# shock_side_control.net
KiCad netlist of a schematic drawn in EAGLE
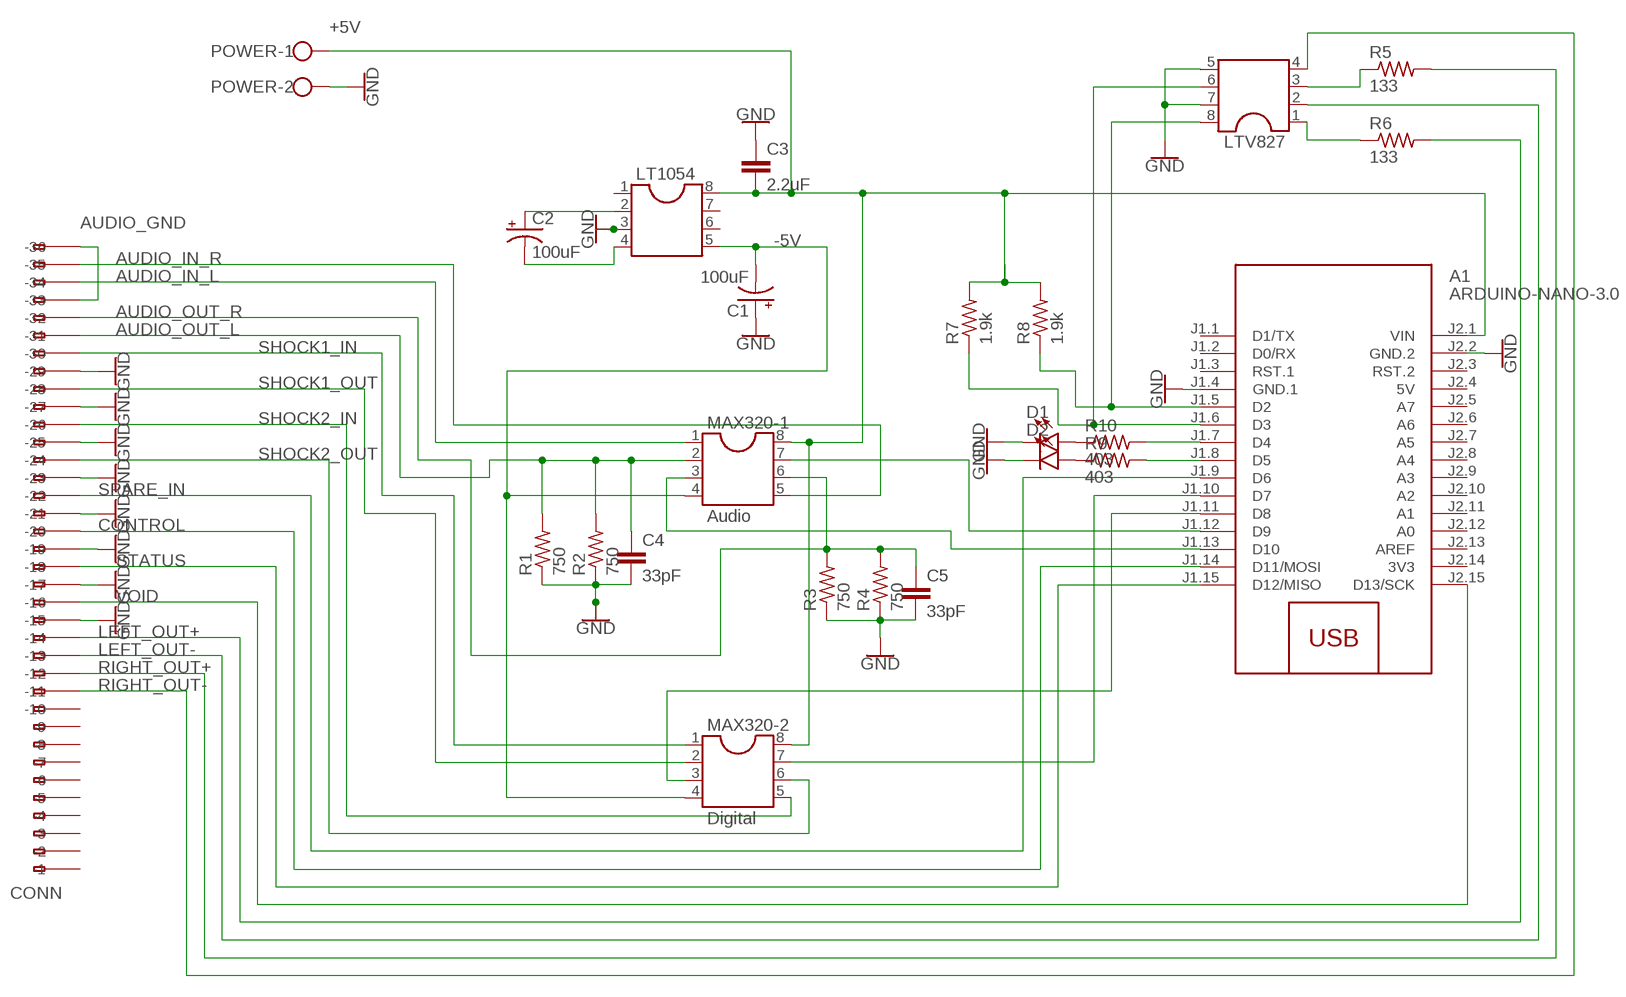
[diagram p0: schematic, sheet 1]

(export (version "E")
  (design (tool "Eeschema 10.0.6"))
  (components
    (comp (ref "A1")
      (value "ARDUINO-NANO-3.0")
      (footprint "eagle-import:ARDUINO-NANO-3.0")
      (libsource (lib "eagle-import") (part "ARDUINO-NANO-3.0"))
    )
    (comp (ref "C1")
      (value "100uF")
      (footprint "eagle-import:CPOL-RADIAL-2.5MM-6.5MM")
      (libsource (lib "eagle-import") (part "100UF-POLAR-RADIAL-2.5MM-25V-20%"))
    )
    (comp (ref "C2")
      (value "100uF")
      (footprint "eagle-import:CPOL-RADIAL-2.5MM-6.5MM")
      (libsource (lib "eagle-import") (part "100UF-POLAR-RADIAL-2.5MM-25V-20%"))
    )
    (comp (ref "C3")
      (value "2.2uF")
      (footprint "eagle-import:C5B2.5")
      (libsource (lib "eagle-import") (part "C5/2.5"))
    )
    (comp (ref "C4")
      (value "33pF")
      (footprint "eagle-import:C5B2.5")
      (libsource (lib "eagle-import") (part "C5/2.5"))
    )
    (comp (ref "C5")
      (value "33pF")
      (footprint "eagle-import:C5B2.5")
      (libsource (lib "eagle-import") (part "C5/2.5"))
    )
    (comp (ref "CONN")
      (value "233-136")
      (footprint "eagle-import:233-136")
      (libsource (lib "eagle-import") (part "233-136"))
    )
    (comp (ref "D1")
      (value "LED-3MM-NO_SILK")
      (footprint "eagle-import:LED_3MM-NS")
      (libsource (lib "eagle-import") (part "LED-3MM-NO_SILK"))
    )
    (comp (ref "D2")
      (value "LED-3MM-NO_SILK")
      (footprint "eagle-import:LED_3MM-NS")
      (libsource (lib "eagle-import") (part "LED-3MM-NO_SILK"))
    )
    (comp (ref "LT1054")
      (value "DIL8")
      (footprint "eagle-import:DIL08")
      (libsource (lib "eagle-import") (part "DIL8"))
    )
    (comp (ref "LTV827")
      (value "DIL8")
      (footprint "eagle-import:DIL08")
      (libsource (lib "eagle-import") (part "DIL8"))
    )
    (comp (ref "MAX320-1")
      (value "Audio")
      (footprint "eagle-import:DIL08")
      (libsource (lib "eagle-import") (part "DIL8"))
    )
    (comp (ref "MAX320-2")
      (value "Digital")
      (footprint "eagle-import:DIL08")
      (libsource (lib "eagle-import") (part "DIL8"))
    )
    (comp (ref "POWER")
      (value "W237-02P")
      (footprint "eagle-import:W237-132")
      (libsource (lib "eagle-import") (part "W237-02P"))
    )
    (comp (ref "R1")
      (value "750")
      (footprint "eagle-import:0805-THM")
      (libsource (lib "eagle-import") (part "FLIPFLOP-RES"))
    )
    (comp (ref "R2")
      (value "750")
      (footprint "eagle-import:0805-THM")
      (libsource (lib "eagle-import") (part "FLIPFLOP-RES"))
    )
    (comp (ref "R3")
      (value "750")
      (footprint "eagle-import:0805-THM")
      (libsource (lib "eagle-import") (part "FLIPFLOP-RES"))
    )
    (comp (ref "R4")
      (value "750")
      (footprint "eagle-import:0805-THM")
      (libsource (lib "eagle-import") (part "FLIPFLOP-RES"))
    )
    (comp (ref "R5")
      (value "133")
      (footprint "eagle-import:0805-THM")
      (libsource (lib "eagle-import") (part "FLIPFLOP-RES"))
    )
    (comp (ref "R6")
      (value "133")
      (footprint "eagle-import:0805-THM")
      (libsource (lib "eagle-import") (part "FLIPFLOP-RES"))
    )
    (comp (ref "R7")
      (value "1.9k")
      (footprint "eagle-import:0805-THM")
      (libsource (lib "eagle-import") (part "FLIPFLOP-RES"))
    )
    (comp (ref "R8")
      (value "1.9k")
      (footprint "eagle-import:0805-THM")
      (libsource (lib "eagle-import") (part "FLIPFLOP-RES"))
    )
    (comp (ref "R9")
      (value "403")
      (footprint "eagle-import:0805-THM")
      (libsource (lib "eagle-import") (part "FLIPFLOP-RES"))
    )
    (comp (ref "R10")
      (value "403")
      (footprint "eagle-import:0805-THM")
      (libsource (lib "eagle-import") (part "FLIPFLOP-RES"))
    )
  )
  (nets
    (net (code "1") (name "/+5V") (class "Default")
      (node (ref "A1") (pin "J2.1") (pinfunction "VIN_J2.1") (pintype "power_in"))
      (node (ref "C3") (pin "2") (pinfunction "2_2") (pintype "passive"))
      (node (ref "LT1054") (pin "8") (pinfunction "8_8") (pintype "passive"))
      (node (ref "MAX320-1") (pin "8") (pinfunction "8_8") (pintype "passive"))
      (node (ref "MAX320-2") (pin "8") (pinfunction "8_8") (pintype "passive"))
      (node (ref "POWER") (pin "1") (pinfunction "KL_1") (pintype "passive"))
      (node (ref "R7") (pin "2") (pinfunction "2_2") (pintype "passive"))
      (node (ref "R8") (pin "2") (pinfunction "2_2") (pintype "passive"))
    )
    (net (code "2") (name "/-5V") (class "Default")
      (node (ref "C1") (pin "2") (pinfunction "-_2") (pintype "passive"))
      (node (ref "LT1054") (pin "5") (pinfunction "5_5") (pintype "passive"))
      (node (ref "MAX320-1") (pin "4") (pinfunction "4_4") (pintype "passive"))
      (node (ref "MAX320-2") (pin "4") (pinfunction "4_4") (pintype "passive"))
    )
    (net (code "3") (name "/3V3") (class "Default")
      (node (ref "A1") (pin "J2.14") (pinfunction "3V3_J2.14") (pintype "power_in"))
    )
    (net (code "4") (name "/5V") (class "Default")
      (node (ref "A1") (pin "J2.4") (pinfunction "5V_J2.4") (pintype "power_in"))
    )
    (net (code "5") (name "/AUDIO_GND") (class "Default")
      (node (ref "CONN") (pin "A33") (pinfunction "-33_A33") (pintype "passive"))
      (node (ref "CONN") (pin "A36") (pinfunction "-36_A36") (pintype "passive"))
    )
    (net (code "6") (name "/AUDIO_IN_L") (class "Default")
      (node (ref "CONN") (pin "A34") (pinfunction "-34_A34") (pintype "passive"))
      (node (ref "MAX320-1") (pin "1") (pinfunction "1_1") (pintype "passive"))
    )
    (net (code "7") (name "/AUDIO_IN_R") (class "Default")
      (node (ref "CONN") (pin "A35") (pinfunction "-35_A35") (pintype "passive"))
      (node (ref "MAX320-1") (pin "5") (pinfunction "5_5") (pintype "passive"))
    )
    (net (code "8") (name "/AUDIO_OUT_L") (class "Default")
      (node (ref "C4") (pin "1") (pinfunction "1_1") (pintype "passive"))
      (node (ref "CONN") (pin "A31") (pinfunction "-31_A31") (pintype "passive"))
      (node (ref "MAX320-1") (pin "2") (pinfunction "2_2") (pintype "passive"))
      (node (ref "R1") (pin "2") (pinfunction "2_2") (pintype "passive"))
      (node (ref "R2") (pin "2") (pinfunction "2_2") (pintype "passive"))
    )
    (net (code "9") (name "/AUDIO_OUT_R") (class "Default")
      (node (ref "C5") (pin "1") (pinfunction "1_1") (pintype "passive"))
      (node (ref "CONN") (pin "A32") (pinfunction "-32_A32") (pintype "passive"))
      (node (ref "MAX320-1") (pin "6") (pinfunction "6_6") (pintype "passive"))
      (node (ref "R3") (pin "2") (pinfunction "2_2") (pintype "passive"))
      (node (ref "R4") (pin "2") (pinfunction "2_2") (pintype "passive"))
    )
    (net (code "10") (name "/CONTROL") (class "Default")
      (node (ref "A1") (pin "J1.14") (pinfunction "D11/MOSI_J1.14") (pintype "bidirectional"))
      (node (ref "CONN") (pin "A20") (pinfunction "-20_A20") (pintype "passive"))
    )
    (net (code "11") (name "/LEFT_OUT+") (class "Default")
      (node (ref "CONN") (pin "A14") (pinfunction "-14_A14") (pintype "passive"))
      (node (ref "R6") (pin "2") (pinfunction "2_2") (pintype "passive"))
    )
    (net (code "12") (name "/LEFT_OUT-") (class "Default")
      (node (ref "CONN") (pin "A13") (pinfunction "-13_A13") (pintype "passive"))
      (node (ref "LTV827") (pin "2") (pinfunction "2_2") (pintype "passive"))
    )
    (net (code "13") (name "/RIGHT_OUT+") (class "Default")
      (node (ref "CONN") (pin "A12") (pinfunction "-12_A12") (pintype "passive"))
      (node (ref "R5") (pin "2") (pinfunction "2_2") (pintype "passive"))
    )
    (net (code "14") (name "/RIGHT_OUT-") (class "Default")
      (node (ref "CONN") (pin "A11") (pinfunction "-11_A11") (pintype "passive"))
      (node (ref "LTV827") (pin "4") (pinfunction "4_4") (pintype "passive"))
    )
    (net (code "15") (name "/SHOCK1_IN") (class "Default")
      (node (ref "CONN") (pin "A30") (pinfunction "-30_A30") (pintype "passive"))
      (node (ref "MAX320-2") (pin "1") (pinfunction "1_1") (pintype "passive"))
    )
    (net (code "16") (name "/SHOCK1_OUT") (class "Default")
      (node (ref "CONN") (pin "A28") (pinfunction "-28_A28") (pintype "passive"))
      (node (ref "MAX320-2") (pin "2") (pinfunction "2_2") (pintype "passive"))
    )
    (net (code "17") (name "/SHOCK2_IN") (class "Default")
      (node (ref "CONN") (pin "A26") (pinfunction "-26_A26") (pintype "passive"))
      (node (ref "MAX320-2") (pin "5") (pinfunction "5_5") (pintype "passive"))
    )
    (net (code "18") (name "/SHOCK2_OUT") (class "Default")
      (node (ref "CONN") (pin "A24") (pinfunction "-24_A24") (pintype "passive"))
      (node (ref "MAX320-2") (pin "6") (pinfunction "6_6") (pintype "passive"))
    )
    (net (code "19") (name "/SPARE_IN") (class "Default")
      (node (ref "A1") (pin "J1.9") (pinfunction "D6_J1.9") (pintype "bidirectional"))
      (node (ref "CONN") (pin "A22") (pinfunction "-22_A22") (pintype "passive"))
    )
    (net (code "20") (name "/STATUS") (class "Default")
      (node (ref "A1") (pin "J1.15") (pinfunction "D12/MISO_J1.15") (pintype "bidirectional"))
      (node (ref "CONN") (pin "A18") (pinfunction "-18_A18") (pintype "passive"))
    )
    (net (code "21") (name "/VOID") (class "Default")
      (node (ref "A1") (pin "J2.15") (pinfunction "D13/SCK_J2.15") (pintype "bidirectional"))
      (node (ref "CONN") (pin "A16") (pinfunction "-16_A16") (pintype "passive"))
    )
    (net (code "22") (name "GND") (class "Default")
      (node (ref "A1") (pin "J1.4") (pinfunction "GND.1_J1.4") (pintype "power_in"))
      (node (ref "A1") (pin "J2.2") (pinfunction "GND.2_J2.2") (pintype "power_in"))
      (node (ref "C1") (pin "1") (pinfunction "+_1") (pintype "passive"))
      (node (ref "C3") (pin "1") (pinfunction "1_1") (pintype "passive"))
      (node (ref "C4") (pin "2") (pinfunction "2_2") (pintype "passive"))
      (node (ref "C5") (pin "2") (pinfunction "2_2") (pintype "passive"))
      (node (ref "CONN") (pin "A15") (pinfunction "-15_A15") (pintype "passive"))
      (node (ref "CONN") (pin "A17") (pinfunction "-17_A17") (pintype "passive"))
      (node (ref "CONN") (pin "A19") (pinfunction "-19_A19") (pintype "passive"))
      (node (ref "CONN") (pin "A21") (pinfunction "-21_A21") (pintype "passive"))
      (node (ref "CONN") (pin "A23") (pinfunction "-23_A23") (pintype "passive"))
      (node (ref "CONN") (pin "A25") (pinfunction "-25_A25") (pintype "passive"))
      (node (ref "CONN") (pin "A27") (pinfunction "-27_A27") (pintype "passive"))
      (node (ref "CONN") (pin "A29") (pinfunction "-29_A29") (pintype "passive"))
      (node (ref "D1") (pin "K") (pinfunction "C_K") (pintype "passive"))
      (node (ref "D2") (pin "K") (pinfunction "C_K") (pintype "passive"))
      (node (ref "LT1054") (pin "3") (pinfunction "3_3") (pintype "passive"))
      (node (ref "LTV827") (pin "5") (pinfunction "5_5") (pintype "passive"))
      (node (ref "LTV827") (pin "7") (pinfunction "7_7") (pintype "passive"))
      (node (ref "POWER") (pin "2") (pinfunction "KL_2") (pintype "passive"))
      (node (ref "R1") (pin "1") (pinfunction "1_1") (pintype "passive"))
      (node (ref "R2") (pin "1") (pinfunction "1_1") (pintype "passive"))
      (node (ref "R3") (pin "1") (pinfunction "1_1") (pintype "passive"))
      (node (ref "R4") (pin "1") (pinfunction "1_1") (pintype "passive"))
    )
    (net (code "23") (name "Net-(A1-D2)") (class "Default")
      (node (ref "A1") (pin "J1.5") (pinfunction "D2_J1.5") (pintype "bidirectional"))
      (node (ref "LTV827") (pin "8") (pinfunction "8_8") (pintype "passive"))
      (node (ref "R8") (pin "1") (pinfunction "1_1") (pintype "passive"))
    )
    (net (code "24") (name "Net-(A1-D3)") (class "Default")
      (node (ref "A1") (pin "J1.6") (pinfunction "D3_J1.6") (pintype "bidirectional"))
      (node (ref "LTV827") (pin "6") (pinfunction "6_6") (pintype "passive"))
      (node (ref "R7") (pin "1") (pinfunction "1_1") (pintype "passive"))
    )
    (net (code "25") (name "Net-(A1-D4)") (class "Default")
      (node (ref "A1") (pin "J1.7") (pinfunction "D4_J1.7") (pintype "bidirectional"))
      (node (ref "R10") (pin "2") (pinfunction "2_2") (pintype "passive"))
    )
    (net (code "26") (name "Net-(A1-D5)") (class "Default")
      (node (ref "A1") (pin "J1.8") (pinfunction "D5_J1.8") (pintype "bidirectional"))
      (node (ref "R9") (pin "2") (pinfunction "2_2") (pintype "passive"))
    )
    (net (code "27") (name "Net-(A1-D7)") (class "Default")
      (node (ref "A1") (pin "J1.10") (pinfunction "D7_J1.10") (pintype "bidirectional"))
      (node (ref "MAX320-2") (pin "7") (pinfunction "7_7") (pintype "passive"))
    )
    (net (code "28") (name "Net-(A1-D8)") (class "Default")
      (node (ref "A1") (pin "J1.11") (pinfunction "D8_J1.11") (pintype "bidirectional"))
      (node (ref "MAX320-2") (pin "3") (pinfunction "3_3") (pintype "passive"))
    )
    (net (code "29") (name "Net-(A1-D9)") (class "Default")
      (node (ref "A1") (pin "J1.12") (pinfunction "D9_J1.12") (pintype "bidirectional"))
      (node (ref "MAX320-1") (pin "7") (pinfunction "7_7") (pintype "passive"))
    )
    (net (code "30") (name "Net-(A1-D10)") (class "Default")
      (node (ref "A1") (pin "J1.13") (pinfunction "D10_J1.13") (pintype "bidirectional"))
      (node (ref "MAX320-1") (pin "3") (pinfunction "3_3") (pintype "passive"))
    )
    (net (code "31") (name "Net-(C2-+)") (class "Default")
      (node (ref "C2") (pin "1") (pinfunction "+_1") (pintype "passive"))
      (node (ref "LT1054") (pin "2") (pinfunction "2_2") (pintype "passive"))
    )
    (net (code "32") (name "Net-(C2--)") (class "Default")
      (node (ref "C2") (pin "2") (pinfunction "-_2") (pintype "passive"))
      (node (ref "LT1054") (pin "4") (pinfunction "4_4") (pintype "passive"))
    )
    (net (code "33") (name "Net-(D1-PadA)") (class "Default")
      (node (ref "D1") (pin "A") (pinfunction "A_A") (pintype "passive"))
      (node (ref "R10") (pin "1") (pinfunction "1_1") (pintype "passive"))
    )
    (net (code "34") (name "Net-(D2-PadA)") (class "Default")
      (node (ref "D2") (pin "A") (pinfunction "A_A") (pintype "passive"))
      (node (ref "R9") (pin "1") (pinfunction "1_1") (pintype "passive"))
    )
    (net (code "35") (name "Net-(LTV827-Pad1)") (class "Default")
      (node (ref "LTV827") (pin "1") (pinfunction "1_1") (pintype "passive"))
      (node (ref "R6") (pin "1") (pinfunction "1_1") (pintype "passive"))
    )
    (net (code "36") (name "Net-(LTV827-Pad3)") (class "Default")
      (node (ref "LTV827") (pin "3") (pinfunction "3_3") (pintype "passive"))
      (node (ref "R5") (pin "1") (pinfunction "1_1") (pintype "passive"))
    )
    (net (code "37") (name "unconnected-(A1-A0-PadJ2.12)") (class "Default")
      (node (ref "A1") (pin "J2.12") (pinfunction "A0_J2.12") (pintype "bidirectional"))
    )
    (net (code "38") (name "unconnected-(A1-A1-PadJ2.11)") (class "Default")
      (node (ref "A1") (pin "J2.11") (pinfunction "A1_J2.11") (pintype "bidirectional"))
    )
    (net (code "39") (name "unconnected-(A1-A2-PadJ2.10)") (class "Default")
      (node (ref "A1") (pin "J2.10") (pinfunction "A2_J2.10") (pintype "bidirectional"))
    )
    (net (code "40") (name "unconnected-(A1-A3-PadJ2.9)") (class "Default")
      (node (ref "A1") (pin "J2.9") (pinfunction "A3_J2.9") (pintype "bidirectional"))
    )
    (net (code "41") (name "unconnected-(A1-A4-PadJ2.8)") (class "Default")
      (node (ref "A1") (pin "J2.8") (pinfunction "A4_J2.8") (pintype "bidirectional"))
    )
    (net (code "42") (name "unconnected-(A1-A5-PadJ2.7)") (class "Default")
      (node (ref "A1") (pin "J2.7") (pinfunction "A5_J2.7") (pintype "bidirectional"))
    )
    (net (code "43") (name "unconnected-(A1-A6-PadJ2.6)") (class "Default")
      (node (ref "A1") (pin "J2.6") (pinfunction "A6_J2.6") (pintype "bidirectional"))
    )
    (net (code "44") (name "unconnected-(A1-A7-PadJ2.5)") (class "Default")
      (node (ref "A1") (pin "J2.5") (pinfunction "A7_J2.5") (pintype "bidirectional"))
    )
    (net (code "45") (name "unconnected-(A1-AREF-PadJ2.13)") (class "Default")
      (node (ref "A1") (pin "J2.13") (pinfunction "AREF_J2.13") (pintype "bidirectional"))
    )
    (net (code "46") (name "unconnected-(A1-D0{slash}RX-PadJ1.2)") (class "Default")
      (node (ref "A1") (pin "J1.2") (pinfunction "D0/RX_J1.2") (pintype "bidirectional"))
    )
    (net (code "47") (name "unconnected-(A1-D1{slash}TX-PadJ1.1)") (class "Default")
      (node (ref "A1") (pin "J1.1") (pinfunction "D1/TX_J1.1") (pintype "bidirectional"))
    )
    (net (code "48") (name "unconnected-(A1-RST.1-PadJ1.3)") (class "Default")
      (node (ref "A1") (pin "J1.3") (pinfunction "RST.1_J1.3") (pintype "bidirectional"))
    )
    (net (code "49") (name "unconnected-(A1-RST.2-PadJ2.3)") (class "Default")
      (node (ref "A1") (pin "J2.3") (pinfunction "RST.2_J2.3") (pintype "bidirectional"))
    )
    (net (code "50") (name "unconnected-(CONN--1-PadA1)") (class "Default")
      (node (ref "CONN") (pin "A1") (pinfunction "-1_A1") (pintype "passive"))
    )
    (net (code "51") (name "unconnected-(CONN--2-PadA2)") (class "Default")
      (node (ref "CONN") (pin "A2") (pinfunction "-2_A2") (pintype "passive"))
    )
    (net (code "52") (name "unconnected-(CONN--3-PadA3)") (class "Default")
      (node (ref "CONN") (pin "A3") (pinfunction "-3_A3") (pintype "passive"))
    )
    (net (code "53") (name "unconnected-(CONN--4-PadA4)") (class "Default")
      (node (ref "CONN") (pin "A4") (pinfunction "-4_A4") (pintype "passive"))
    )
    (net (code "54") (name "unconnected-(CONN--5-PadA5)") (class "Default")
      (node (ref "CONN") (pin "A5") (pinfunction "-5_A5") (pintype "passive"))
    )
    (net (code "55") (name "unconnected-(CONN--6-PadA6)") (class "Default")
      (node (ref "CONN") (pin "A6") (pinfunction "-6_A6") (pintype "passive"))
    )
    (net (code "56") (name "unconnected-(CONN--7-PadA7)") (class "Default")
      (node (ref "CONN") (pin "A7") (pinfunction "-7_A7") (pintype "passive"))
    )
    (net (code "57") (name "unconnected-(CONN--8-PadA8)") (class "Default")
      (node (ref "CONN") (pin "A8") (pinfunction "-8_A8") (pintype "passive"))
    )
    (net (code "58") (name "unconnected-(CONN--9-PadA9)") (class "Default")
      (node (ref "CONN") (pin "A9") (pinfunction "-9_A9") (pintype "passive"))
    )
    (net (code "59") (name "unconnected-(CONN--10-PadA10)") (class "Default")
      (node (ref "CONN") (pin "A10") (pinfunction "-10_A10") (pintype "passive"))
    )
    (net (code "60") (name "unconnected-(CONN-B-1-PadB1)") (class "Default")
      (node (ref "CONN") (pin "B1") (pinfunction "B-1_B1") (pintype "passive"))
    )
    (net (code "61") (name "unconnected-(CONN-B-2-PadB2)") (class "Default")
      (node (ref "CONN") (pin "B2") (pinfunction "B-2_B2") (pintype "passive"))
    )
    (net (code "62") (name "unconnected-(CONN-B-3-PadB3)") (class "Default")
      (node (ref "CONN") (pin "B3") (pinfunction "B-3_B3") (pintype "passive"))
    )
    (net (code "63") (name "unconnected-(CONN-B-4-PadB4)") (class "Default")
      (node (ref "CONN") (pin "B4") (pinfunction "B-4_B4") (pintype "passive"))
    )
    (net (code "64") (name "unconnected-(CONN-B-5-PadB5)") (class "Default")
      (node (ref "CONN") (pin "B5") (pinfunction "B-5_B5") (pintype "passive"))
    )
    (net (code "65") (name "unconnected-(CONN-B-6-PadB6)") (class "Default")
      (node (ref "CONN") (pin "B6") (pinfunction "B-6_B6") (pintype "passive"))
    )
    (net (code "66") (name "unconnected-(CONN-B-7-PadB7)") (class "Default")
      (node (ref "CONN") (pin "B7") (pinfunction "B-7_B7") (pintype "passive"))
    )
    (net (code "67") (name "unconnected-(CONN-B-8-PadB8)") (class "Default")
      (node (ref "CONN") (pin "B8") (pinfunction "B-8_B8") (pintype "passive"))
    )
    (net (code "68") (name "unconnected-(CONN-B-9-PadB9)") (class "Default")
      (node (ref "CONN") (pin "B9") (pinfunction "B-9_B9") (pintype "passive"))
    )
    (net (code "69") (name "unconnected-(CONN-B-10-PadB10)") (class "Default")
      (node (ref "CONN") (pin "B10") (pinfunction "B-10_B10") (pintype "passive"))
    )
    (net (code "70") (name "unconnected-(CONN-B-11-PadB11)") (class "Default")
      (node (ref "CONN") (pin "B11") (pinfunction "B-11_B11") (pintype "passive"))
    )
    (net (code "71") (name "unconnected-(CONN-B-12-PadB12)") (class "Default")
      (node (ref "CONN") (pin "B12") (pinfunction "B-12_B12") (pintype "passive"))
    )
    (net (code "72") (name "unconnected-(CONN-B-13-PadB13)") (class "Default")
      (node (ref "CONN") (pin "B13") (pinfunction "B-13_B13") (pintype "passive"))
    )
    (net (code "73") (name "unconnected-(CONN-B-14-PadB14)") (class "Default")
      (node (ref "CONN") (pin "B14") (pinfunction "B-14_B14") (pintype "passive"))
    )
    (net (code "74") (name "unconnected-(CONN-B-15-PadB15)") (class "Default")
      (node (ref "CONN") (pin "B15") (pinfunction "B-15_B15") (pintype "passive"))
    )
    (net (code "75") (name "unconnected-(CONN-B-16-PadB16)") (class "Default")
      (node (ref "CONN") (pin "B16") (pinfunction "B-16_B16") (pintype "passive"))
    )
    (net (code "76") (name "unconnected-(CONN-B-17-PadB17)") (class "Default")
      (node (ref "CONN") (pin "B17") (pinfunction "B-17_B17") (pintype "passive"))
    )
    (net (code "77") (name "unconnected-(CONN-B-18-PadB18)") (class "Default")
      (node (ref "CONN") (pin "B18") (pinfunction "B-18_B18") (pintype "passive"))
    )
    (net (code "78") (name "unconnected-(CONN-B-19-PadB19)") (class "Default")
      (node (ref "CONN") (pin "B19") (pinfunction "B-19_B19") (pintype "passive"))
    )
    (net (code "79") (name "unconnected-(CONN-B-20-PadB20)") (class "Default")
      (node (ref "CONN") (pin "B20") (pinfunction "B-20_B20") (pintype "passive"))
    )
    (net (code "80") (name "unconnected-(CONN-B-21-PadB21)") (class "Default")
      (node (ref "CONN") (pin "B21") (pinfunction "B-21_B21") (pintype "passive"))
    )
    (net (code "81") (name "unconnected-(CONN-B-22-PadB22)") (class "Default")
      (node (ref "CONN") (pin "B22") (pinfunction "B-22_B22") (pintype "passive"))
    )
    (net (code "82") (name "unconnected-(CONN-B-23-PadB23)") (class "Default")
      (node (ref "CONN") (pin "B23") (pinfunction "B-23_B23") (pintype "passive"))
    )
    (net (code "83") (name "unconnected-(CONN-B-24-PadB24)") (class "Default")
      (node (ref "CONN") (pin "B24") (pinfunction "B-24_B24") (pintype "passive"))
    )
    (net (code "84") (name "unconnected-(CONN-B-25-PadB25)") (class "Default")
      (node (ref "CONN") (pin "B25") (pinfunction "B-25_B25") (pintype "passive"))
    )
    (net (code "85") (name "unconnected-(CONN-B-26-PadB26)") (class "Default")
      (node (ref "CONN") (pin "B26") (pinfunction "B-26_B26") (pintype "passive"))
    )
    (net (code "86") (name "unconnected-(CONN-B-27-PadB27)") (class "Default")
      (node (ref "CONN") (pin "B27") (pinfunction "B-27_B27") (pintype "passive"))
    )
    (net (code "87") (name "unconnected-(CONN-B-28-PadB28)") (class "Default")
      (node (ref "CONN") (pin "B28") (pinfunction "B-28_B28") (pintype "passive"))
    )
    (net (code "88") (name "unconnected-(CONN-B-29-PadB29)") (class "Default")
      (node (ref "CONN") (pin "B29") (pinfunction "B-29_B29") (pintype "passive"))
    )
    (net (code "89") (name "unconnected-(CONN-B-30-PadB30)") (class "Default")
      (node (ref "CONN") (pin "B30") (pinfunction "B-30_B30") (pintype "passive"))
    )
    (net (code "90") (name "unconnected-(CONN-B-31-PadB31)") (class "Default")
      (node (ref "CONN") (pin "B31") (pinfunction "B-31_B31") (pintype "passive"))
    )
    (net (code "91") (name "unconnected-(CONN-B-32-PadB32)") (class "Default")
      (node (ref "CONN") (pin "B32") (pinfunction "B-32_B32") (pintype "passive"))
    )
    (net (code "92") (name "unconnected-(CONN-B-33-PadB33)") (class "Default")
      (node (ref "CONN") (pin "B33") (pinfunction "B-33_B33") (pintype "passive"))
    )
    (net (code "93") (name "unconnected-(CONN-B-34-PadB34)") (class "Default")
      (node (ref "CONN") (pin "B34") (pinfunction "B-34_B34") (pintype "passive"))
    )
    (net (code "94") (name "unconnected-(CONN-B-35-PadB35)") (class "Default")
      (node (ref "CONN") (pin "B35") (pinfunction "B-35_B35") (pintype "passive"))
    )
    (net (code "95") (name "unconnected-(CONN-B-36-PadB36)") (class "Default")
      (node (ref "CONN") (pin "B36") (pinfunction "B-36_B36") (pintype "passive"))
    )
    (net (code "96") (name "unconnected-(LT1054-Pad1)") (class "Default")
      (node (ref "LT1054") (pin "1") (pinfunction "1_1") (pintype "passive"))
    )
    (net (code "97") (name "unconnected-(LT1054-Pad6)") (class "Default")
      (node (ref "LT1054") (pin "6") (pinfunction "6_6") (pintype "passive"))
    )
    (net (code "98") (name "unconnected-(LT1054-Pad7)") (class "Default")
      (node (ref "LT1054") (pin "7") (pinfunction "7_7") (pintype "passive"))
    )
  )
)
